# USBserial.net
KiCad netlist of a schematic drawn in Altium Designer
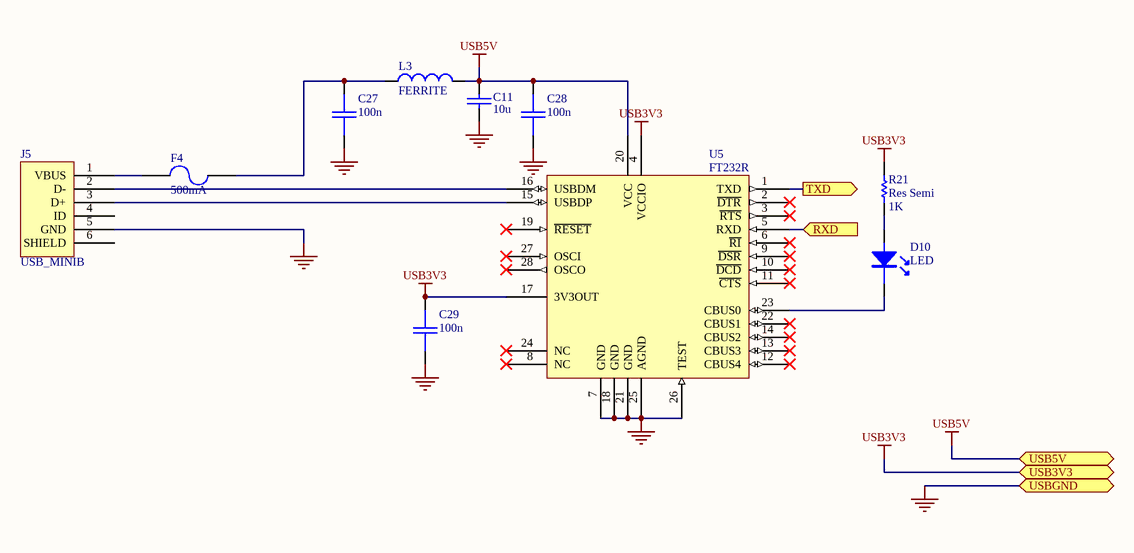
[diagram p0: USBserial.SchDoc]

(export (version "E")
  (design (tool "Eeschema 10.0.6"))
  (components
    (comp (ref "C11")
      (value "10u")
      (footprint "0805")
      (description "Capacitor")
      (libsource (lib "*") (part "CAP"))
    )
    (comp (ref "C27")
      (value "100n")
      (footprint "0603")
      (description "Capacitor")
      (libsource (lib "RCLDQ") (part "CAP"))
    )
    (comp (ref "C28")
      (value "100n")
      (footprint "0603")
      (description "Capacitor")
      (libsource (lib "RCLDQ") (part "CAP"))
    )
    (comp (ref "C29")
      (value "100n")
      (footprint "0603")
      (description "Capacitor")
      (libsource (lib "RCLDQ") (part "CAP"))
    )
    (comp (ref "D10") (value "LED") (footprint "3mmLED") (libsource (lib "RCLDQ") (part "LED")))
    (comp (ref "F4")
      (value "500mA")
      (footprint "LITTELFUSE-154")
      (description "Fuse")
      (libsource (lib "*") (part "FUSE2"))
    )
    (comp (ref "J5")
      (value "USB_MINIB")
      (footprint "USB_MINIB")
      (description "USB Mini B Connector")
      (libsource (lib "sion") (part "USB_miniB_SMT"))
    )
    (comp (ref "L3")
      (value "FERRITE")
      (footprint "0805")
      (description "Inductor")
      (fields (field (name "MANUFACTURER") "Generic Components"))
      (libsource (lib "RCLDQ") (part "INDUCTOR"))
    )
    (comp (ref "R21")
      (value "Res Semi")
      (footprint "1608[0603]")
      (description "Semiconductor Resistor")
      (fields (field (name "ALTIUM_VALUE") "1K"))
      (libsource (lib "Miscellaneous Devices") (part "Res Semi"))
    )
    (comp (ref "U5")
      (value "FT232R")
      (footprint "SSOP28")
      (description "USB UART IC")
      (libsource (lib "MiscellaneousIC") (part "FT232R"))
    )
  )
  (nets
    (net (code "1") (name "/RXD") (class "Default")
      (node (ref "U5") (pin "5") (pinfunction "RXD_5") (pintype "input"))
    )
    (net (code "2") (name "/TXD") (class "Default")
      (node (ref "U5") (pin "1") (pinfunction "TXD_1") (pintype "output"))
    )
    (net (code "3") (name "Net-(C27-Pad1)") (class "Default")
      (node (ref "C27") (pin "1") (pinfunction "1_1") (pintype "passive"))
      (node (ref "F4") (pin "2") (pinfunction "2_2") (pintype "passive"))
      (node (ref "L3") (pin "1") (pinfunction "1_1") (pintype "passive"))
    )
    (net (code "4") (name "Net-(D10-PadA)") (class "Default")
      (node (ref "D10") (pin "A") (pinfunction "A_A") (pintype "passive"))
      (node (ref "R21") (pin "1") (pinfunction "1_1") (pintype "passive"))
    )
    (net (code "5") (name "Net-(J5-D+)") (class "Default")
      (node (ref "J5") (pin "3") (pinfunction "D+_3") (pintype "passive"))
      (node (ref "U5") (pin "15") (pinfunction "USBDP_15") (pintype "bidirectional"))
    )
    (net (code "6") (name "Net-(J5-D-)") (class "Default")
      (node (ref "J5") (pin "2") (pinfunction "D-_2") (pintype "passive"))
      (node (ref "U5") (pin "16") (pinfunction "USBDM_16") (pintype "bidirectional"))
    )
    (net (code "7") (name "Net-(J5-VBUS)") (class "Default")
      (node (ref "F4") (pin "1") (pinfunction "1_1") (pintype "passive"))
      (node (ref "J5") (pin "1") (pinfunction "VBUS_1") (pintype "passive"))
    )
    (net (code "8") (name "Net-(U5-CBUS0)") (class "Default")
      (node (ref "D10") (pin "K") (pinfunction "K_K") (pintype "passive"))
      (node (ref "U5") (pin "23") (pinfunction "CBUS0_23") (pintype "bidirectional"))
    )
    (net (code "9") (name "USB3V3") (class "Default")
      (node (ref "C29") (pin "1") (pinfunction "1_1") (pintype "passive"))
      (node (ref "R21") (pin "2") (pinfunction "2_2") (pintype "passive"))
      (node (ref "U5") (pin "17") (pinfunction "3V3OUT_17") (pintype "power_in"))
      (node (ref "U5") (pin "4") (pinfunction "VCCIO_4") (pintype "power_in"))
    )
    (net (code "10") (name "USB5V") (class "Default")
      (node (ref "C11") (pin "2") (pinfunction "2_2") (pintype "passive"))
      (node (ref "C28") (pin "1") (pinfunction "1_1") (pintype "passive"))
      (node (ref "L3") (pin "2") (pinfunction "2_2") (pintype "passive"))
      (node (ref "U5") (pin "20") (pinfunction "VCC_20") (pintype "power_in"))
    )
    (net (code "11") (name "USBGND") (class "Default")
      (node (ref "C11") (pin "1") (pinfunction "1_1") (pintype "passive"))
      (node (ref "C27") (pin "2") (pinfunction "2_2") (pintype "passive"))
      (node (ref "C28") (pin "2") (pinfunction "2_2") (pintype "passive"))
      (node (ref "C29") (pin "2") (pinfunction "2_2") (pintype "passive"))
      (node (ref "J5") (pin "5") (pinfunction "GND_5") (pintype "passive"))
      (node (ref "U5") (pin "18") (pinfunction "GND_18") (pintype "power_in"))
      (node (ref "U5") (pin "21") (pinfunction "GND_21") (pintype "power_in"))
      (node (ref "U5") (pin "25") (pinfunction "AGND_25") (pintype "power_in"))
      (node (ref "U5") (pin "26") (pinfunction "TEST_26") (pintype "input"))
      (node (ref "U5") (pin "7") (pinfunction "GND_7") (pintype "power_in"))
    )
    (net (code "12") (name "unconnected-(J5-ID-Pad4)") (class "Default")
      (node (ref "J5") (pin "4") (pinfunction "ID_4") (pintype "passive"))
    )
    (net (code "13") (name "unconnected-(J5-SHIELD-Pad6)") (class "Default")
      (node (ref "J5") (pin "6") (pinfunction "SHIELD_6") (pintype "passive"))
    )
    (net (code "14") (name "unconnected-(U5-CBUS1-Pad22)") (class "Default")
      (node (ref "U5") (pin "22") (pinfunction "CBUS1_22") (pintype "bidirectional+no_connect"))
    )
    (net (code "15") (name "unconnected-(U5-CBUS2-Pad14)") (class "Default")
      (node (ref "U5") (pin "14") (pinfunction "CBUS2_14") (pintype "bidirectional+no_connect"))
    )
    (net (code "16") (name "unconnected-(U5-CBUS3-Pad13)") (class "Default")
      (node (ref "U5") (pin "13") (pinfunction "CBUS3_13") (pintype "bidirectional+no_connect"))
    )
    (net (code "17") (name "unconnected-(U5-CBUS4-Pad12)") (class "Default")
      (node (ref "U5") (pin "12") (pinfunction "CBUS4_12") (pintype "bidirectional+no_connect"))
    )
    (net (code "18") (name "unconnected-(U5-NC-Pad8)") (class "Default")
      (node (ref "U5") (pin "8") (pinfunction "NC_8") (pintype "passive+no_connect"))
    )
    (net (code "19") (name "unconnected-(U5-NC-Pad24)") (class "Default")
      (node (ref "U5") (pin "24") (pinfunction "NC_24") (pintype "passive+no_connect"))
    )
    (net (code "20") (name "unconnected-(U5-OSCI-Pad27)") (class "Default")
      (node (ref "U5") (pin "27") (pinfunction "OSCI_27") (pintype "input+no_connect"))
    )
    (net (code "21") (name "unconnected-(U5-OSCO-Pad28)") (class "Default")
      (node (ref "U5") (pin "28") (pinfunction "OSCO_28") (pintype "output+no_connect"))
    )
    (net (code "22") (name "unconnected-(U5-~{CTS}-Pad11)") (class "Default")
      (node (ref "U5") (pin "11") (pinfunction "~{CTS}_11") (pintype "input+no_connect"))
    )
    (net (code "23") (name "unconnected-(U5-~{DCD}-Pad10)") (class "Default")
      (node (ref "U5") (pin "10") (pinfunction "~{DCD}_10") (pintype "input+no_connect"))
    )
    (net (code "24") (name "unconnected-(U5-~{DSR}-Pad9)") (class "Default")
      (node (ref "U5") (pin "9") (pinfunction "~{DSR}_9") (pintype "input+no_connect"))
    )
    (net (code "25") (name "unconnected-(U5-~{DTR}-Pad2)") (class "Default")
      (node (ref "U5") (pin "2") (pinfunction "~{DTR}_2") (pintype "output+no_connect"))
    )
    (net (code "26") (name "unconnected-(U5-~{RESET}-Pad19)") (class "Default")
      (node (ref "U5") (pin "19") (pinfunction "~{RESET}_19") (pintype "input+no_connect"))
    )
    (net (code "27") (name "unconnected-(U5-~{RI}-Pad6)") (class "Default")
      (node (ref "U5") (pin "6") (pinfunction "~{RI}_6") (pintype "input+no_connect"))
    )
    (net (code "28") (name "unconnected-(U5-~{RTS}-Pad3)") (class "Default")
      (node (ref "U5") (pin "3") (pinfunction "~{RTS}_3") (pintype "output+no_connect"))
    )
  )
)
